# DWM1000_Basic_Board.net
KiCad netlist of a schematic drawn in Altium Designer
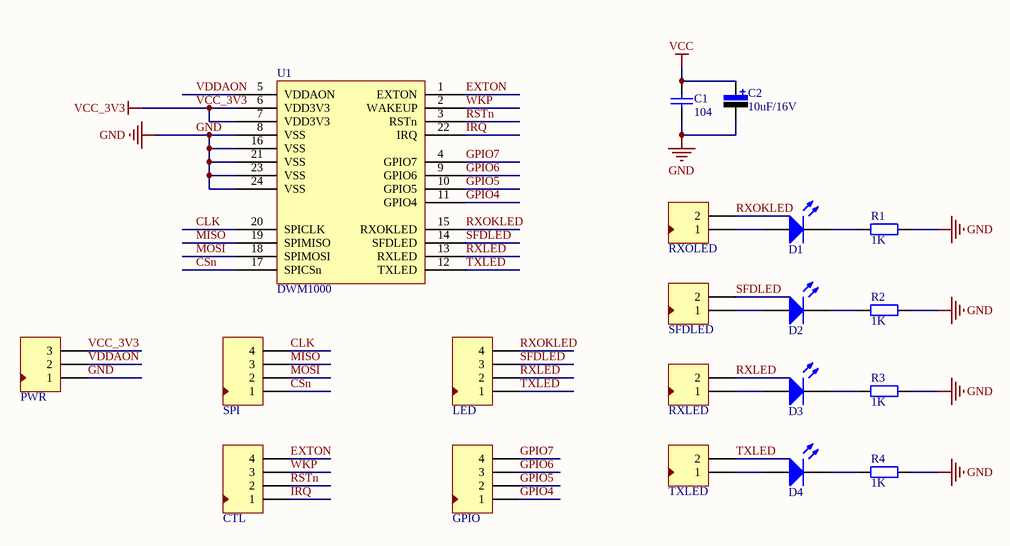
[diagram p0: DWM1000_Basic_Board.SchDoc]

(export (version "E")
  (design (tool "Eeschema 10.0.6"))
  (components
    (comp (ref "C1")
      (value "104")
      (footprint "C-0603")
      (description "贴片瓷片电容")
      (fields (field (name "Comment") "Cap-S") (field (name "PUBLISHER") "Altium Limited"))
      (libsource (lib "Fszhang") (part "Cap-S"))
    )
    (comp (ref "C2")
      (value "10uF/16V")
      (footprint "1206")
      (description "贴片电解电容")
      (fields (field (name "Comment") "Cap-Pol") (field (name "PUBLISHER") "Altium Limited"))
      (libsource (lib "HanZ_Library") (part "Cap-Pol"))
    )
    (comp (ref "CTL")
      (value "Header 4")
      (footprint "HDR4X1-2.54")
      (description "接插件")
      (fields (field (name "PUBLISHER") "Altium Limited"))
      (libsource (lib "HDR_Fszhang") (part "Header 4"))
    )
    (comp (ref "D1")
      (value "LED0")
      (footprint "0603-1")
      (description "发光二极管")
      (fields (field (name "PUBLISHER") "Altium Limited"))
      (libsource (lib "HanZ_Library") (part "LED0"))
    )
    (comp (ref "D2")
      (value "LED0")
      (footprint "0603-1")
      (description "发光二极管")
      (fields (field (name "PUBLISHER") "Altium Limited"))
      (libsource (lib "HanZ_Library") (part "LED0"))
    )
    (comp (ref "D3")
      (value "LED0")
      (footprint "0603-1")
      (description "发光二极管")
      (fields (field (name "PUBLISHER") "Altium Limited"))
      (libsource (lib "HanZ_Library") (part "LED0"))
    )
    (comp (ref "D4")
      (value "LED0")
      (footprint "0603-1")
      (description "发光二极管")
      (fields (field (name "PUBLISHER") "Altium Limited"))
      (libsource (lib "HanZ_Library") (part "LED0"))
    )
    (comp (ref "GPIO")
      (value "Header 4")
      (footprint "XH2.54-4P")
      (description "接插件")
      (fields (field (name "PUBLISHER") "Altium Limited"))
      (libsource (lib "HDR_Fszhang") (part "Header 4"))
    )
    (comp (ref "LED")
      (value "Header 4")
      (footprint "XH2.54-4P")
      (description "接插件")
      (fields (field (name "PUBLISHER") "Altium Limited"))
      (libsource (lib "HDR_Fszhang") (part "Header 4"))
    )
    (comp (ref "PWR")
      (value "Header 3")
      (footprint "HDR3X1-2.54")
      (description "接插件")
      (fields (field (name "PUBLISHER") "Altium Limited"))
      (libsource (lib "HDR_Fszhang") (part "Header 3"))
    )
    (comp (ref "R1")
      (value "1K")
      (footprint "0603-1")
      (description "贴片电阻")
      (fields (field (name "Comment") "Res1") (field (name "PUBLISHER") "Altium Limited"))
      (libsource (lib "Fszhang") (part "Res1"))
    )
    (comp (ref "R2")
      (value "1K")
      (footprint "0603-1")
      (description "贴片电阻")
      (fields (field (name "Comment") "Res1") (field (name "PUBLISHER") "Altium Limited"))
      (libsource (lib "Fszhang") (part "Res1"))
    )
    (comp (ref "R3")
      (value "1K")
      (footprint "0603-1")
      (description "贴片电阻")
      (fields (field (name "Comment") "Res1") (field (name "PUBLISHER") "Altium Limited"))
      (libsource (lib "Fszhang") (part "Res1"))
    )
    (comp (ref "R4")
      (value "1K")
      (footprint "0603-1")
      (description "贴片电阻")
      (fields (field (name "Comment") "Res1") (field (name "PUBLISHER") "Altium Limited"))
      (libsource (lib "Fszhang") (part "Res1"))
    )
    (comp (ref "RXLED")
      (value "Header 2")
      (footprint "HDR2X1-2.54")
      (description "接插件")
      (fields (field (name "PUBLISHER") "Altium Limited"))
      (libsource (lib "HDR_Fszhang") (part "Header 2"))
    )
    (comp (ref "RXOLED")
      (value "Header 2")
      (footprint "HDR2X1-2.54")
      (description "接插件")
      (fields (field (name "PUBLISHER") "Altium Limited"))
      (libsource (lib "HDR_Fszhang") (part "Header 2"))
    )
    (comp (ref "SFDLED")
      (value "Header 2")
      (footprint "HDR2X1-2.54")
      (description "接插件")
      (fields (field (name "PUBLISHER") "Altium Limited"))
      (libsource (lib "HDR_Fszhang") (part "Header 2"))
    )
    (comp (ref "SPI")
      (value "Header 4")
      (footprint "HDR4X1-2.54")
      (description "接插件")
      (fields (field (name "PUBLISHER") "Altium Limited"))
      (libsource (lib "HDR_Fszhang") (part "Header 4"))
    )
    (comp (ref "TXLED")
      (value "Header 2")
      (footprint "HDR2X1-2.54")
      (description "接插件")
      (fields (field (name "PUBLISHER") "Altium Limited"))
      (libsource (lib "HDR_Fszhang") (part "Header 2"))
    )
    (comp (ref "U1")
      (value "DWM1000")
      (footprint "DWM1000")
      (libsource (lib "HanZ_Library") (part "DWM1000"))
    )
  )
  (nets
    (net (code "1") (name "/CLK") (class "Default")
      (node (ref "SPI") (pin "4") (pinfunction "4_4") (pintype "passive"))
      (node (ref "U1") (pin "20") (pinfunction "SPICLK_20") (pintype "passive"))
    )
    (net (code "2") (name "/CSn") (class "Default")
      (node (ref "SPI") (pin "1") (pinfunction "1_1") (pintype "passive"))
      (node (ref "U1") (pin "17") (pinfunction "SPICSn_17") (pintype "passive"))
    )
    (net (code "3") (name "/EXTON") (class "Default")
      (node (ref "CTL") (pin "4") (pinfunction "4_4") (pintype "passive"))
      (node (ref "U1") (pin "1") (pinfunction "EXTON_1") (pintype "passive"))
    )
    (net (code "4") (name "/GPIO4") (class "Default")
      (node (ref "GPIO") (pin "1") (pinfunction "1_1") (pintype "passive"))
      (node (ref "U1") (pin "11") (pinfunction "GPIO4_11") (pintype "passive"))
    )
    (net (code "5") (name "/GPIO5") (class "Default")
      (node (ref "GPIO") (pin "2") (pinfunction "2_2") (pintype "passive"))
      (node (ref "U1") (pin "10") (pinfunction "GPIO5_10") (pintype "passive"))
    )
    (net (code "6") (name "/GPIO6") (class "Default")
      (node (ref "GPIO") (pin "3") (pinfunction "3_3") (pintype "passive"))
      (node (ref "U1") (pin "9") (pinfunction "GPIO6_9") (pintype "passive"))
    )
    (net (code "7") (name "/GPIO7") (class "Default")
      (node (ref "GPIO") (pin "4") (pinfunction "4_4") (pintype "passive"))
      (node (ref "U1") (pin "4") (pinfunction "GPIO7_4") (pintype "passive"))
    )
    (net (code "8") (name "/IRQ") (class "Default")
      (node (ref "CTL") (pin "1") (pinfunction "1_1") (pintype "passive"))
      (node (ref "U1") (pin "22") (pinfunction "IRQ_22") (pintype "passive"))
    )
    (net (code "9") (name "/MISO") (class "Default")
      (node (ref "SPI") (pin "3") (pinfunction "3_3") (pintype "passive"))
      (node (ref "U1") (pin "19") (pinfunction "SPIMISO_19") (pintype "passive"))
    )
    (net (code "10") (name "/MOSI") (class "Default")
      (node (ref "SPI") (pin "2") (pinfunction "2_2") (pintype "passive"))
      (node (ref "U1") (pin "18") (pinfunction "SPIMOSI_18") (pintype "passive"))
    )
    (net (code "11") (name "/RSTn") (class "Default")
      (node (ref "CTL") (pin "2") (pinfunction "2_2") (pintype "passive"))
      (node (ref "U1") (pin "3") (pinfunction "RSTn_3") (pintype "passive"))
    )
    (net (code "12") (name "/RXLED") (class "Default")
      (node (ref "LED") (pin "2") (pinfunction "2_2") (pintype "passive"))
      (node (ref "RXLED") (pin "2") (pinfunction "2_2") (pintype "passive"))
      (node (ref "U1") (pin "13") (pinfunction "RXLED_13") (pintype "passive"))
    )
    (net (code "13") (name "/RXOKLED") (class "Default")
      (node (ref "LED") (pin "4") (pinfunction "4_4") (pintype "passive"))
      (node (ref "RXOLED") (pin "2") (pinfunction "2_2") (pintype "passive"))
      (node (ref "U1") (pin "15") (pinfunction "RXOKLED_15") (pintype "passive"))
    )
    (net (code "14") (name "/SFDLED") (class "Default")
      (node (ref "LED") (pin "3") (pinfunction "3_3") (pintype "passive"))
      (node (ref "SFDLED") (pin "2") (pinfunction "2_2") (pintype "passive"))
      (node (ref "U1") (pin "14") (pinfunction "SFDLED_14") (pintype "passive"))
    )
    (net (code "15") (name "/TXLED") (class "Default")
      (node (ref "LED") (pin "1") (pinfunction "1_1") (pintype "passive"))
      (node (ref "TXLED") (pin "2") (pinfunction "2_2") (pintype "passive"))
      (node (ref "U1") (pin "12") (pinfunction "TXLED_12") (pintype "passive"))
    )
    (net (code "16") (name "/VDDAON") (class "Default")
      (node (ref "PWR") (pin "2") (pinfunction "2_2") (pintype "passive"))
      (node (ref "U1") (pin "5") (pinfunction "VDDAON_5") (pintype "passive"))
    )
    (net (code "17") (name "/WKP") (class "Default")
      (node (ref "CTL") (pin "3") (pinfunction "3_3") (pintype "passive"))
      (node (ref "U1") (pin "2") (pinfunction "WAKEUP_2") (pintype "passive"))
    )
    (net (code "18") (name "GND") (class "Default")
      (node (ref "C1") (pin "1") (pinfunction "1_1") (pintype "passive"))
      (node (ref "C2") (pin "2") (pinfunction "2_2") (pintype "passive"))
      (node (ref "PWR") (pin "1") (pinfunction "1_1") (pintype "passive"))
      (node (ref "R1") (pin "2") (pinfunction "2_2") (pintype "passive"))
      (node (ref "R2") (pin "2") (pinfunction "2_2") (pintype "passive"))
      (node (ref "R3") (pin "2") (pinfunction "2_2") (pintype "passive"))
      (node (ref "R4") (pin "2") (pinfunction "2_2") (pintype "passive"))
      (node (ref "U1") (pin "16") (pinfunction "VSS_16") (pintype "passive"))
      (node (ref "U1") (pin "21") (pinfunction "VSS_21") (pintype "passive"))
      (node (ref "U1") (pin "23") (pinfunction "VSS_23") (pintype "passive"))
      (node (ref "U1") (pin "24") (pinfunction "VSS_24") (pintype "passive"))
      (node (ref "U1") (pin "8") (pinfunction "VSS_8") (pintype "passive"))
    )
    (net (code "19") (name "Net-(D1-A)") (class "Default")
      (node (ref "D1") (pin "1") (pinfunction "A_1") (pintype "passive"))
      (node (ref "RXOLED") (pin "1") (pinfunction "1_1") (pintype "passive"))
    )
    (net (code "20") (name "Net-(D1-K)") (class "Default")
      (node (ref "D1") (pin "2") (pinfunction "K_2") (pintype "passive"))
      (node (ref "R1") (pin "1") (pinfunction "1_1") (pintype "passive"))
    )
    (net (code "21") (name "Net-(D2-A)") (class "Default")
      (node (ref "D2") (pin "1") (pinfunction "A_1") (pintype "passive"))
      (node (ref "SFDLED") (pin "1") (pinfunction "1_1") (pintype "passive"))
    )
    (net (code "22") (name "Net-(D2-K)") (class "Default")
      (node (ref "D2") (pin "2") (pinfunction "K_2") (pintype "passive"))
      (node (ref "R2") (pin "1") (pinfunction "1_1") (pintype "passive"))
    )
    (net (code "23") (name "Net-(D3-A)") (class "Default")
      (node (ref "D3") (pin "1") (pinfunction "A_1") (pintype "passive"))
      (node (ref "RXLED") (pin "1") (pinfunction "1_1") (pintype "passive"))
    )
    (net (code "24") (name "Net-(D3-K)") (class "Default")
      (node (ref "D3") (pin "2") (pinfunction "K_2") (pintype "passive"))
      (node (ref "R3") (pin "1") (pinfunction "1_1") (pintype "passive"))
    )
    (net (code "25") (name "Net-(D4-A)") (class "Default")
      (node (ref "D4") (pin "1") (pinfunction "A_1") (pintype "passive"))
      (node (ref "TXLED") (pin "1") (pinfunction "1_1") (pintype "passive"))
    )
    (net (code "26") (name "Net-(D4-K)") (class "Default")
      (node (ref "D4") (pin "2") (pinfunction "K_2") (pintype "passive"))
      (node (ref "R4") (pin "1") (pinfunction "1_1") (pintype "passive"))
    )
    (net (code "27") (name "VCC") (class "Default")
      (node (ref "C1") (pin "2") (pinfunction "2_2") (pintype "passive"))
      (node (ref "C2") (pin "1") (pinfunction "1_1") (pintype "passive"))
    )
    (net (code "28") (name "VCC_3V3") (class "Default")
      (node (ref "PWR") (pin "3") (pinfunction "3_3") (pintype "passive"))
      (node (ref "U1") (pin "6") (pinfunction "VDD3V3_6") (pintype "passive"))
      (node (ref "U1") (pin "7") (pinfunction "VDD3V3_7") (pintype "passive"))
    )
  )
)
